# 8w_usb_soldering_iron.net
KiCad netlist of a schematic drawn in EAGLE
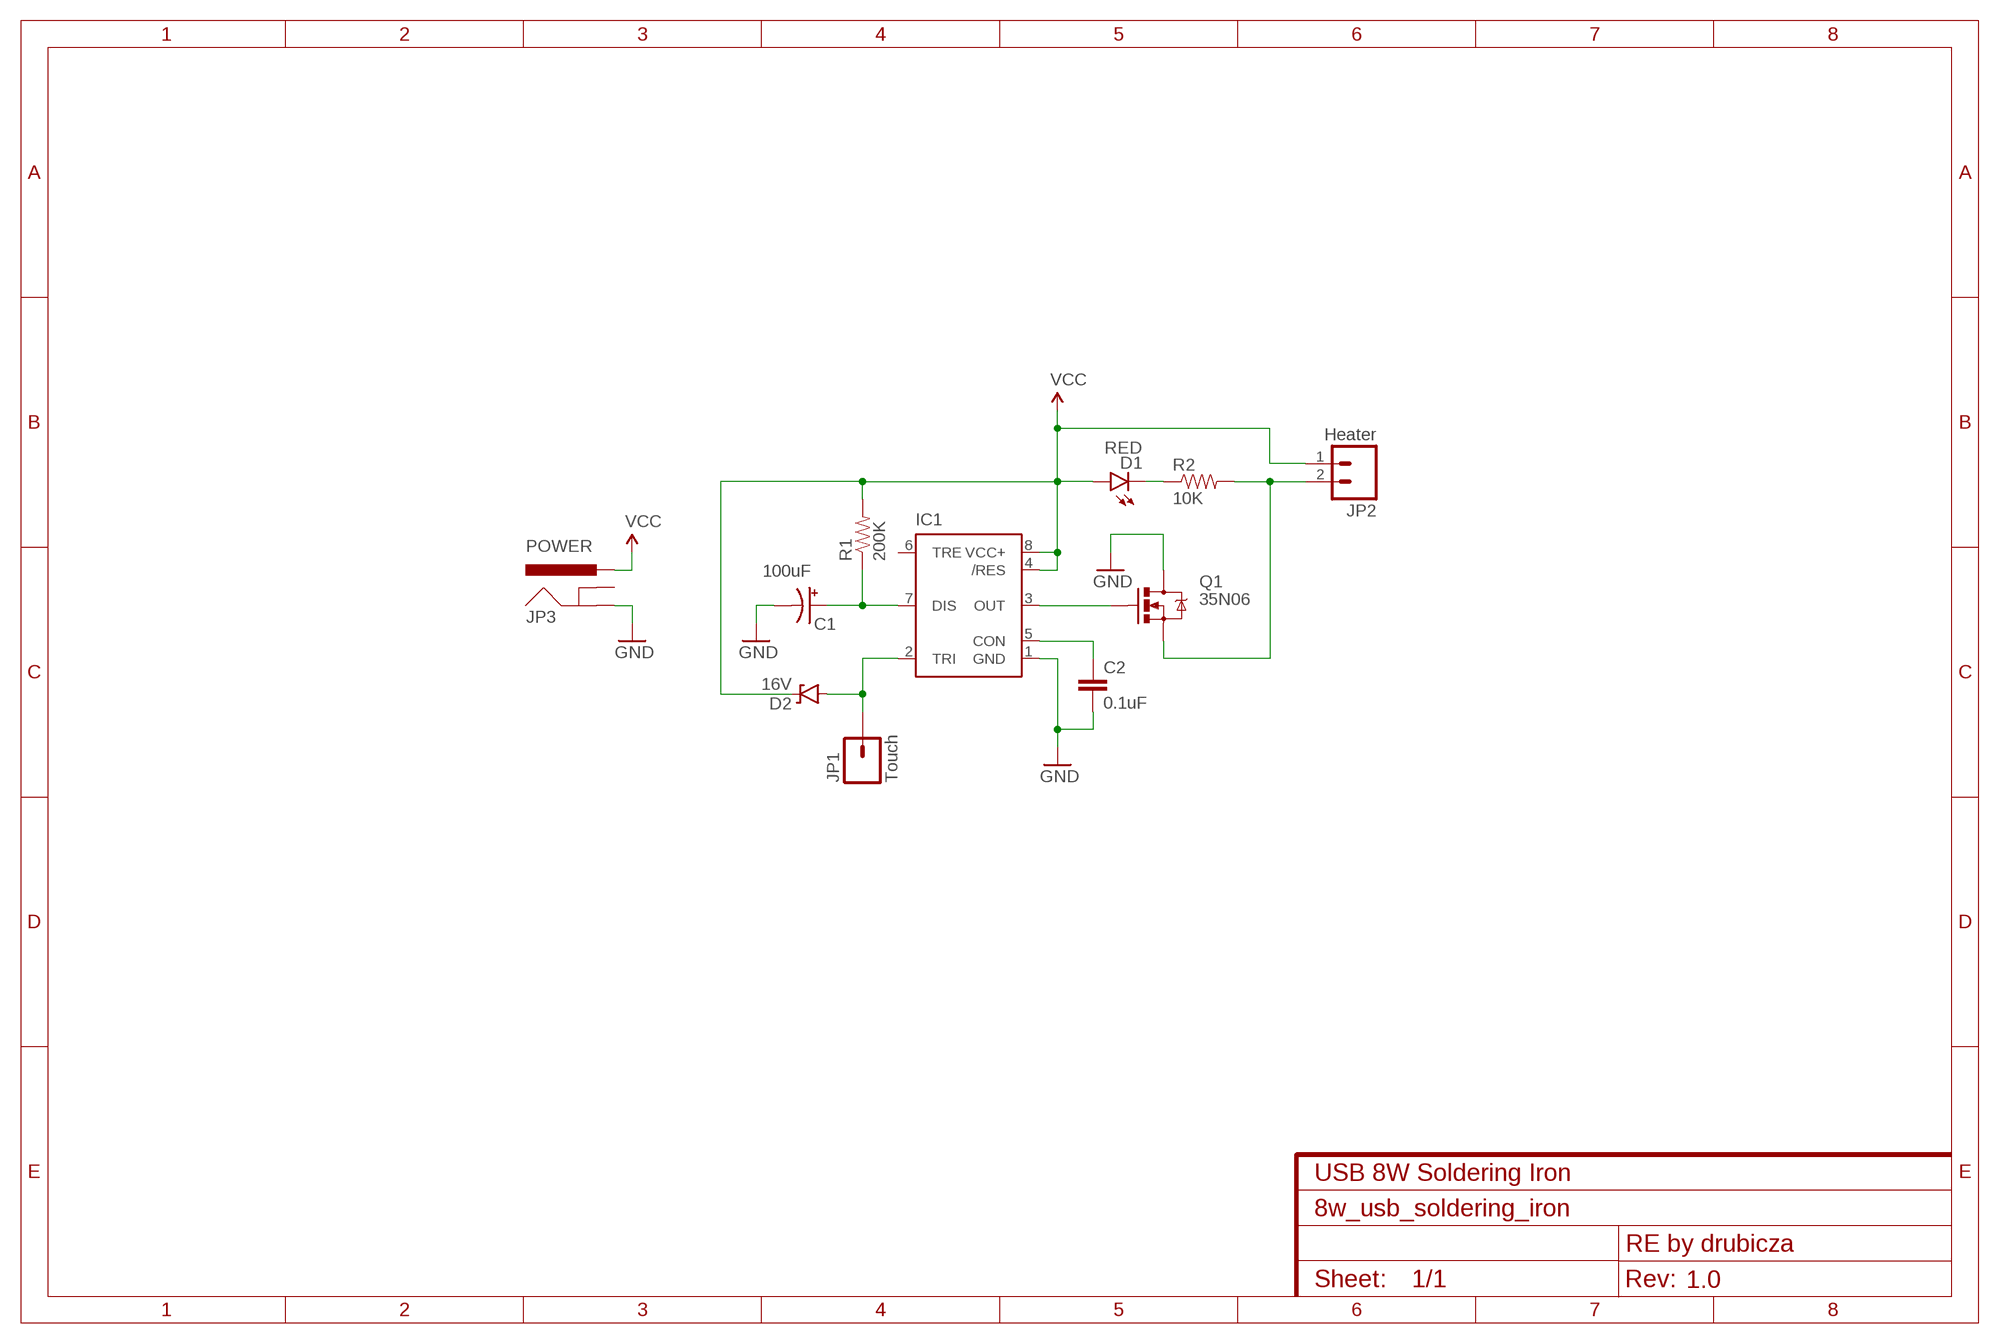
[diagram p0: schematic, sheet 1]

(export (version "E")
  (design (tool "Eeschema 10.0.6"))
  (components
    (comp (ref "C1")
      (value "100uF")
      (footprint "eagle-import:CPOL-RADIAL-100UF-25V")
      (libsource (lib "eagle-import") (part "CAP_POLPTH1"))
    )
    (comp (ref "C2")
      (value "0.1uF")
      (footprint "eagle-import:0805")
      (libsource (lib "eagle-import") (part "CAP0805"))
    )
    (comp (ref "D1")
      (value "RED")
      (footprint "eagle-import:LED3MM")
      (libsource (lib "eagle-import") (part "LED3MM"))
    )
    (comp (ref "D2")
      (value "16V")
      (footprint "eagle-import:SOD-123")
      (libsource (lib "eagle-import") (part "DIODE-ZENER16V"))
    )
    (comp (ref "IC1")
      (value "NE555D")
      (footprint "eagle-import:SO08")
      (libsource (lib "eagle-import") (part "NE555D"))
    )
    (comp (ref "JP1")
      (value "Touch")
      (footprint "eagle-import:1X01")
      (libsource (lib "eagle-import") (part "M01PTH"))
    )
    (comp (ref "JP2")
      (value "Heater")
      (footprint "eagle-import:1X02")
      (libsource (lib "eagle-import") (part "M02PTH"))
    )
    (comp (ref "JP3")
      (value "POWER")
      (footprint "eagle-import:POWER_JACK_PTH")
      (libsource (lib "eagle-import") (part "POWER_JACKPTH"))
    )
    (comp (ref "Q1")
      (value "35N06")
      (footprint "eagle-import:TO220V")
      (libsource (lib "eagle-import") (part "MOSFET-NCHANNELFQP30N06L"))
    )
    (comp (ref "R1")
      (value "200K")
      (footprint "eagle-import:0603-RES")
      (libsource (lib "eagle-import") (part "RESISTOR0603-RES"))
    )
    (comp (ref "R2")
      (value "10K")
      (footprint "eagle-import:0603-RES")
      (libsource (lib "eagle-import") (part "RESISTOR0603-RES"))
    )
  )
  (nets
    (net (code "1") (name "GND") (class "Default")
      (node (ref "C1") (pin "2") (pinfunction "-_2") (pintype "passive"))
      (node (ref "C2") (pin "2") (pinfunction "2_2") (pintype "passive"))
      (node (ref "IC1") (pin "1") (pinfunction "GND_1") (pintype "power_in"))
      (node (ref "JP3") (pin "GND") (pinfunction "GND_GND") (pintype "bidirectional"))
      (node (ref "Q1") (pin "2") (pinfunction "D_2") (pintype "passive"))
    )
    (net (code "2") (name "Net-(C1-+)") (class "Default")
      (node (ref "C1") (pin "1") (pinfunction "+_1") (pintype "passive"))
      (node (ref "IC1") (pin "7") (pinfunction "DIS_7") (pintype "input"))
      (node (ref "R1") (pin "1") (pinfunction "1_1") (pintype "passive"))
    )
    (net (code "3") (name "Net-(D1-C)") (class "Default")
      (node (ref "D1") (pin "K") (pinfunction "C_K") (pintype "passive"))
      (node (ref "R2") (pin "1") (pinfunction "1_1") (pintype "passive"))
    )
    (net (code "4") (name "Net-(IC1-CON)") (class "Default")
      (node (ref "C2") (pin "1") (pinfunction "1_1") (pintype "passive"))
      (node (ref "IC1") (pin "5") (pinfunction "CON_5") (pintype "input"))
    )
    (net (code "5") (name "Net-(IC1-OUT)") (class "Default")
      (node (ref "IC1") (pin "3") (pinfunction "OUT_3") (pintype "output"))
      (node (ref "Q1") (pin "1") (pinfunction "G_1") (pintype "passive"))
    )
    (net (code "6") (name "Net-(IC1-TRI)") (class "Default")
      (node (ref "D2") (pin "A") (pinfunction "A_A") (pintype "passive"))
      (node (ref "IC1") (pin "2") (pinfunction "TRI_2") (pintype "input"))
      (node (ref "JP1") (pin "1") (pinfunction "1_1") (pintype "passive"))
    )
    (net (code "7") (name "Net-(Q1-S)") (class "Default")
      (node (ref "JP2") (pin "2") (pinfunction "2_2") (pintype "passive"))
      (node (ref "Q1") (pin "3") (pinfunction "S_3") (pintype "passive"))
      (node (ref "R2") (pin "2") (pinfunction "2_2") (pintype "passive"))
    )
    (net (code "8") (name "VCC") (class "Default")
      (node (ref "D1") (pin "A") (pinfunction "A_A") (pintype "passive"))
      (node (ref "D2") (pin "C") (pinfunction "C_C") (pintype "passive"))
      (node (ref "IC1") (pin "4") (pinfunction "/RES_4") (pintype "input"))
      (node (ref "IC1") (pin "8") (pinfunction "VCC+_8") (pintype "power_in"))
      (node (ref "JP2") (pin "1") (pinfunction "1_1") (pintype "passive"))
      (node (ref "JP3") (pin "PWR") (pinfunction "PWR_PWR") (pintype "bidirectional"))
      (node (ref "R1") (pin "2") (pinfunction "2_2") (pintype "passive"))
    )
    (net (code "9") (name "unconnected-(IC1-TRE-Pad6)") (class "Default")
      (node (ref "IC1") (pin "6") (pinfunction "TRE_6") (pintype "input"))
    )
    (net (code "10") (name "unconnected-(JP3-PadGNDBREAK)") (class "Default")
      (node (ref "JP3") (pin "GNDBREAK") (pinfunction "GNDBREAK_GNDBREAK") (pintype "bidirectional"))
    )
  )
)
